# Anthophora.net
KiCad netlist of a schematic drawn in EAGLE
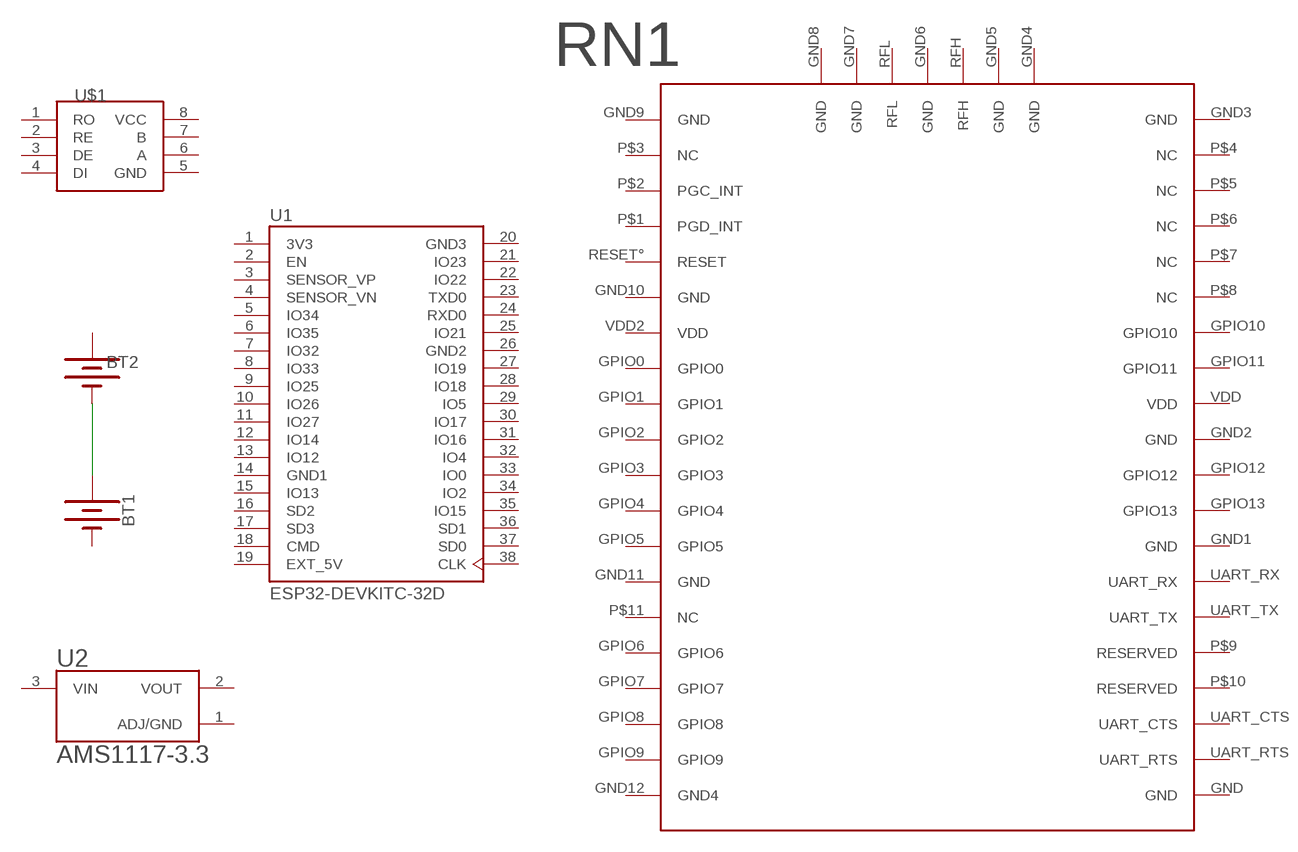
[diagram p0: schematic, sheet 1]

(export (version "E")
  (design (tool "Eeschema 10.0.6"))
  (components
    (comp (ref "BT1")
      (value "BATTERY-AA_KIT")
      (footprint "eagle-import:BATTERY-AA-KIT")
      (libsource (lib "eagle-import") (part "BATTERY-AA_KIT"))
    )
    (comp (ref "BT2")
      (value "BATTERY-AA_KIT")
      (footprint "eagle-import:BATTERY-AA-KIT")
      (libsource (lib "eagle-import") (part "BATTERY-AA_KIT"))
    )
    (comp (ref "RN1")
      (value "NEW_RN2483")
      (footprint "eagle-import:NEW_RN2483")
      (libsource (lib "eagle-import") (part "NEW_RN2483"))
    )
    (comp (ref "U$1")
      (value "AMD3485E")
      (footprint "eagle-import:AMD3485E")
      (libsource (lib "eagle-import") (part "AMD3485E"))
    )
    (comp (ref "U1")
      (value "ESP32-DEVKITC-32D")
      (footprint "eagle-import:MODULE_ESP32-DEVKITC-32D")
      (fields (field (name "MF") "Espressif Systems"))
      (libsource (lib "eagle-import") (part "ESP32-DEVKITC-32D"))
    )
    (comp (ref "U2")
      (value "AMS1117-3.3")
      (footprint "eagle-import:SOT229P700X180-4N")
      (fields (field (name "MF") "Advanced Monolithic Systems"))
      (libsource (lib "eagle-import") (part "AMS1117-3.3"))
    )
  )
  (nets
    (net (code "1") (name "/+") (class "Default")
      (node (ref "BT2") (pin "PWR@1") (pinfunction "+_PWR@1") (pintype "power_in"))
    )
    (net (code "2") (name "/-") (class "Default")
      (node (ref "BT1") (pin "GND@1") (pinfunction "-_GND@1") (pintype "power_in"))
    )
    (net (code "3") (name "/3V3") (class "Default")
      (node (ref "U1") (pin "1") (pinfunction "3V3_1") (pintype "power_in"))
    )
    (net (code "4") (name "/ADJ{slash}GND") (class "Default")
      (node (ref "U2") (pin "1") (pinfunction "ADJ/GND_1") (pintype "power_in"))
    )
    (net (code "5") (name "/EXT_5V") (class "Default")
      (node (ref "U1") (pin "19") (pinfunction "EXT_5V_19") (pintype "power_in"))
    )
    (net (code "6") (name "/GND1") (class "Default")
      (node (ref "U1") (pin "14") (pinfunction "GND1_14") (pintype "power_in"))
    )
    (net (code "7") (name "/GND2") (class "Default")
      (node (ref "U1") (pin "26") (pinfunction "GND2_26") (pintype "power_in"))
    )
    (net (code "8") (name "/GND3") (class "Default")
      (node (ref "U1") (pin "20") (pinfunction "GND3_20") (pintype "power_in"))
    )
    (net (code "9") (name "Net-(BT1-+)") (class "Default")
      (node (ref "BT1") (pin "PWR@1") (pinfunction "+_PWR@1") (pintype "power_in"))
      (node (ref "BT2") (pin "GND@1") (pinfunction "-_GND@1") (pintype "power_in"))
    )
    (net (code "10") (name "unconnected-(RN1-GND-PadGND1)") (class "Default")
      (node (ref "RN1") (pin "GND1") (pinfunction "GND_GND1") (pintype "bidirectional"))
    )
    (net (code "11") (name "unconnected-(RN1-GND-PadGND2)") (class "Default")
      (node (ref "RN1") (pin "GND2") (pinfunction "GND_GND2") (pintype "bidirectional"))
    )
    (net (code "12") (name "unconnected-(RN1-GND-PadGND3)") (class "Default")
      (node (ref "RN1") (pin "GND3") (pinfunction "GND_GND3") (pintype "bidirectional"))
    )
    (net (code "13") (name "unconnected-(RN1-GND-PadGND4)") (class "Default")
      (node (ref "RN1") (pin "GND4") (pinfunction "GND_GND4") (pintype "bidirectional"))
    )
    (net (code "14") (name "unconnected-(RN1-GND-PadGND5)") (class "Default")
      (node (ref "RN1") (pin "GND5") (pinfunction "GND_GND5") (pintype "bidirectional"))
    )
    (net (code "15") (name "unconnected-(RN1-GND-PadGND6)") (class "Default")
      (node (ref "RN1") (pin "GND6") (pinfunction "GND_GND6") (pintype "bidirectional"))
    )
    (net (code "16") (name "unconnected-(RN1-GND-PadGND7)") (class "Default")
      (node (ref "RN1") (pin "GND7") (pinfunction "GND_GND7") (pintype "bidirectional"))
    )
    (net (code "17") (name "unconnected-(RN1-GND-PadGND8)") (class "Default")
      (node (ref "RN1") (pin "GND8") (pinfunction "GND_GND8") (pintype "bidirectional"))
    )
    (net (code "18") (name "unconnected-(RN1-GND-PadGND9)") (class "Default")
      (node (ref "RN1") (pin "GND9") (pinfunction "GND_GND9") (pintype "bidirectional"))
    )
    (net (code "19") (name "unconnected-(RN1-GND-PadGND10)") (class "Default")
      (node (ref "RN1") (pin "GND10") (pinfunction "GND_GND10") (pintype "bidirectional"))
    )
    (net (code "20") (name "unconnected-(RN1-GND-PadGND11)") (class "Default")
      (node (ref "RN1") (pin "GND11") (pinfunction "GND_GND11") (pintype "bidirectional"))
    )
    (net (code "21") (name "unconnected-(RN1-GND4-PadGND12)") (class "Default")
      (node (ref "RN1") (pin "GND12") (pinfunction "GND4_GND12") (pintype "bidirectional"))
    )
    (net (code "22") (name "unconnected-(RN1-NC-PadP$3)") (class "Default")
      (node (ref "RN1") (pin "P$3") (pinfunction "NC_P$3") (pintype "bidirectional"))
    )
    (net (code "23") (name "unconnected-(RN1-NC-PadP$4)") (class "Default")
      (node (ref "RN1") (pin "P$4") (pinfunction "NC_P$4") (pintype "bidirectional"))
    )
    (net (code "24") (name "unconnected-(RN1-NC-PadP$5)") (class "Default")
      (node (ref "RN1") (pin "P$5") (pinfunction "NC_P$5") (pintype "bidirectional"))
    )
    (net (code "25") (name "unconnected-(RN1-NC-PadP$6)") (class "Default")
      (node (ref "RN1") (pin "P$6") (pinfunction "NC_P$6") (pintype "bidirectional"))
    )
    (net (code "26") (name "unconnected-(RN1-NC-PadP$7)") (class "Default")
      (node (ref "RN1") (pin "P$7") (pinfunction "NC_P$7") (pintype "bidirectional"))
    )
    (net (code "27") (name "unconnected-(RN1-NC-PadP$8)") (class "Default")
      (node (ref "RN1") (pin "P$8") (pinfunction "NC_P$8") (pintype "bidirectional"))
    )
    (net (code "28") (name "unconnected-(RN1-NC-PadP$11)") (class "Default")
      (node (ref "RN1") (pin "P$11") (pinfunction "NC_P$11") (pintype "bidirectional"))
    )
    (net (code "29") (name "unconnected-(RN1-PGC_INT-PadP$2)") (class "Default")
      (node (ref "RN1") (pin "P$2") (pinfunction "PGC_INT_P$2") (pintype "bidirectional"))
    )
    (net (code "30") (name "unconnected-(RN1-PGD_INT-PadP$1)") (class "Default")
      (node (ref "RN1") (pin "P$1") (pinfunction "PGD_INT_P$1") (pintype "bidirectional"))
    )
    (net (code "31") (name "unconnected-(RN1-PadGND)") (class "Default")
      (node (ref "RN1") (pin "GND") (pinfunction "GND_GND") (pintype "bidirectional"))
    )
    (net (code "32") (name "unconnected-(RN1-PadGPIO0)") (class "Default")
      (node (ref "RN1") (pin "GPIO0") (pinfunction "GPIO0_GPIO0") (pintype "bidirectional"))
    )
    (net (code "33") (name "unconnected-(RN1-PadGPIO1)") (class "Default")
      (node (ref "RN1") (pin "GPIO1") (pinfunction "GPIO1_GPIO1") (pintype "bidirectional"))
    )
    (net (code "34") (name "unconnected-(RN1-PadGPIO2)") (class "Default")
      (node (ref "RN1") (pin "GPIO2") (pinfunction "GPIO2_GPIO2") (pintype "bidirectional"))
    )
    (net (code "35") (name "unconnected-(RN1-PadGPIO3)") (class "Default")
      (node (ref "RN1") (pin "GPIO3") (pinfunction "GPIO3_GPIO3") (pintype "bidirectional"))
    )
    (net (code "36") (name "unconnected-(RN1-PadGPIO4)") (class "Default")
      (node (ref "RN1") (pin "GPIO4") (pinfunction "GPIO4_GPIO4") (pintype "bidirectional"))
    )
    (net (code "37") (name "unconnected-(RN1-PadGPIO5)") (class "Default")
      (node (ref "RN1") (pin "GPIO5") (pinfunction "GPIO5_GPIO5") (pintype "bidirectional"))
    )
    (net (code "38") (name "unconnected-(RN1-PadGPIO6)") (class "Default")
      (node (ref "RN1") (pin "GPIO6") (pinfunction "GPIO6_GPIO6") (pintype "bidirectional"))
    )
    (net (code "39") (name "unconnected-(RN1-PadGPIO7)") (class "Default")
      (node (ref "RN1") (pin "GPIO7") (pinfunction "GPIO7_GPIO7") (pintype "bidirectional"))
    )
    (net (code "40") (name "unconnected-(RN1-PadGPIO8)") (class "Default")
      (node (ref "RN1") (pin "GPIO8") (pinfunction "GPIO8_GPIO8") (pintype "bidirectional"))
    )
    (net (code "41") (name "unconnected-(RN1-PadGPIO9)") (class "Default")
      (node (ref "RN1") (pin "GPIO9") (pinfunction "GPIO9_GPIO9") (pintype "bidirectional"))
    )
    (net (code "42") (name "unconnected-(RN1-PadGPIO10)") (class "Default")
      (node (ref "RN1") (pin "GPIO10") (pinfunction "GPIO10_GPIO10") (pintype "bidirectional"))
    )
    (net (code "43") (name "unconnected-(RN1-PadGPIO11)") (class "Default")
      (node (ref "RN1") (pin "GPIO11") (pinfunction "GPIO11_GPIO11") (pintype "bidirectional"))
    )
    (net (code "44") (name "unconnected-(RN1-PadGPIO12)") (class "Default")
      (node (ref "RN1") (pin "GPIO12") (pinfunction "GPIO12_GPIO12") (pintype "bidirectional"))
    )
    (net (code "45") (name "unconnected-(RN1-PadGPIO13)") (class "Default")
      (node (ref "RN1") (pin "GPIO13") (pinfunction "GPIO13_GPIO13") (pintype "bidirectional"))
    )
    (net (code "46") (name "unconnected-(RN1-PadRFH)") (class "Default")
      (node (ref "RN1") (pin "RFH") (pinfunction "RFH_RFH") (pintype "bidirectional"))
    )
    (net (code "47") (name "unconnected-(RN1-PadRFL)") (class "Default")
      (node (ref "RN1") (pin "RFL") (pinfunction "RFL_RFL") (pintype "bidirectional"))
    )
    (net (code "48") (name "unconnected-(RN1-PadUART_CTS)") (class "Default")
      (node (ref "RN1") (pin "UART_CTS") (pinfunction "UART_CTS_UART_CTS") (pintype "bidirectional"))
    )
    (net (code "49") (name "unconnected-(RN1-PadUART_RTS)") (class "Default")
      (node (ref "RN1") (pin "UART_RTS") (pinfunction "UART_RTS_UART_RTS") (pintype "bidirectional"))
    )
    (net (code "50") (name "unconnected-(RN1-PadUART_RX)") (class "Default")
      (node (ref "RN1") (pin "UART_RX") (pinfunction "UART_RX_UART_RX") (pintype "bidirectional"))
    )
    (net (code "51") (name "unconnected-(RN1-PadUART_TX)") (class "Default")
      (node (ref "RN1") (pin "UART_TX") (pinfunction "UART_TX_UART_TX") (pintype "bidirectional"))
    )
    (net (code "52") (name "unconnected-(RN1-PadVDD)") (class "Default")
      (node (ref "RN1") (pin "VDD") (pinfunction "VDD_VDD") (pintype "bidirectional"))
    )
    (net (code "53") (name "unconnected-(RN1-RESERVED-PadP$9)") (class "Default")
      (node (ref "RN1") (pin "P$9") (pinfunction "RESERVED_P$9") (pintype "bidirectional"))
    )
    (net (code "54") (name "unconnected-(RN1-RESERVED-PadP$10)") (class "Default")
      (node (ref "RN1") (pin "P$10") (pinfunction "RESERVED_P$10") (pintype "bidirectional"))
    )
    (net (code "55") (name "unconnected-(RN1-RESET-PadRESET°)") (class "Default")
      (node (ref "RN1") (pin "RESET°") (pinfunction "RESET_RESET°") (pintype "bidirectional"))
    )
    (net (code "56") (name "unconnected-(RN1-VDD-PadVDD2)") (class "Default")
      (node (ref "RN1") (pin "VDD2") (pinfunction "VDD_VDD2") (pintype "bidirectional"))
    )
    (net (code "57") (name "unconnected-(U$1-A-Pad6)") (class "Default")
      (node (ref "U$1") (pin "6") (pinfunction "A_6") (pintype "bidirectional"))
    )
    (net (code "58") (name "unconnected-(U$1-B-Pad7)") (class "Default")
      (node (ref "U$1") (pin "7") (pinfunction "B_7") (pintype "bidirectional"))
    )
    (net (code "59") (name "unconnected-(U$1-DE-Pad3)") (class "Default")
      (node (ref "U$1") (pin "3") (pinfunction "DE_3") (pintype "bidirectional"))
    )
    (net (code "60") (name "unconnected-(U$1-DI-Pad4)") (class "Default")
      (node (ref "U$1") (pin "4") (pinfunction "DI_4") (pintype "bidirectional"))
    )
    (net (code "61") (name "unconnected-(U$1-GND-Pad5)") (class "Default")
      (node (ref "U$1") (pin "5") (pinfunction "GND_5") (pintype "bidirectional"))
    )
    (net (code "62") (name "unconnected-(U$1-RE-Pad2)") (class "Default")
      (node (ref "U$1") (pin "2") (pinfunction "RE_2") (pintype "bidirectional"))
    )
    (net (code "63") (name "unconnected-(U$1-RO-Pad1)") (class "Default")
      (node (ref "U$1") (pin "1") (pinfunction "RO_1") (pintype "bidirectional"))
    )
    (net (code "64") (name "unconnected-(U$1-VCC-Pad8)") (class "Default")
      (node (ref "U$1") (pin "8") (pinfunction "VCC_8") (pintype "bidirectional"))
    )
    (net (code "65") (name "unconnected-(U1-CLK-Pad38)") (class "Default")
      (node (ref "U1") (pin "38") (pinfunction "CLK_38") (pintype "input"))
    )
    (net (code "66") (name "unconnected-(U1-CMD-Pad18)") (class "Default")
      (node (ref "U1") (pin "18") (pinfunction "CMD_18") (pintype "bidirectional"))
    )
    (net (code "67") (name "unconnected-(U1-EN-Pad2)") (class "Default")
      (node (ref "U1") (pin "2") (pinfunction "EN_2") (pintype "input"))
    )
    (net (code "68") (name "unconnected-(U1-IO0-Pad33)") (class "Default")
      (node (ref "U1") (pin "33") (pinfunction "IO0_33") (pintype "bidirectional"))
    )
    (net (code "69") (name "unconnected-(U1-IO2-Pad34)") (class "Default")
      (node (ref "U1") (pin "34") (pinfunction "IO2_34") (pintype "bidirectional"))
    )
    (net (code "70") (name "unconnected-(U1-IO4-Pad32)") (class "Default")
      (node (ref "U1") (pin "32") (pinfunction "IO4_32") (pintype "bidirectional"))
    )
    (net (code "71") (name "unconnected-(U1-IO5-Pad29)") (class "Default")
      (node (ref "U1") (pin "29") (pinfunction "IO5_29") (pintype "bidirectional"))
    )
    (net (code "72") (name "unconnected-(U1-IO12-Pad13)") (class "Default")
      (node (ref "U1") (pin "13") (pinfunction "IO12_13") (pintype "bidirectional"))
    )
    (net (code "73") (name "unconnected-(U1-IO13-Pad15)") (class "Default")
      (node (ref "U1") (pin "15") (pinfunction "IO13_15") (pintype "bidirectional"))
    )
    (net (code "74") (name "unconnected-(U1-IO14-Pad12)") (class "Default")
      (node (ref "U1") (pin "12") (pinfunction "IO14_12") (pintype "bidirectional"))
    )
    (net (code "75") (name "unconnected-(U1-IO15-Pad35)") (class "Default")
      (node (ref "U1") (pin "35") (pinfunction "IO15_35") (pintype "bidirectional"))
    )
    (net (code "76") (name "unconnected-(U1-IO16-Pad31)") (class "Default")
      (node (ref "U1") (pin "31") (pinfunction "IO16_31") (pintype "bidirectional"))
    )
    (net (code "77") (name "unconnected-(U1-IO17-Pad30)") (class "Default")
      (node (ref "U1") (pin "30") (pinfunction "IO17_30") (pintype "bidirectional"))
    )
    (net (code "78") (name "unconnected-(U1-IO18-Pad28)") (class "Default")
      (node (ref "U1") (pin "28") (pinfunction "IO18_28") (pintype "bidirectional"))
    )
    (net (code "79") (name "unconnected-(U1-IO19-Pad27)") (class "Default")
      (node (ref "U1") (pin "27") (pinfunction "IO19_27") (pintype "bidirectional"))
    )
    (net (code "80") (name "unconnected-(U1-IO21-Pad25)") (class "Default")
      (node (ref "U1") (pin "25") (pinfunction "IO21_25") (pintype "bidirectional"))
    )
    (net (code "81") (name "unconnected-(U1-IO22-Pad22)") (class "Default")
      (node (ref "U1") (pin "22") (pinfunction "IO22_22") (pintype "bidirectional"))
    )
    (net (code "82") (name "unconnected-(U1-IO23-Pad21)") (class "Default")
      (node (ref "U1") (pin "21") (pinfunction "IO23_21") (pintype "bidirectional"))
    )
    (net (code "83") (name "unconnected-(U1-IO25-Pad9)") (class "Default")
      (node (ref "U1") (pin "9") (pinfunction "IO25_9") (pintype "bidirectional"))
    )
    (net (code "84") (name "unconnected-(U1-IO26-Pad10)") (class "Default")
      (node (ref "U1") (pin "10") (pinfunction "IO26_10") (pintype "bidirectional"))
    )
    (net (code "85") (name "unconnected-(U1-IO27-Pad11)") (class "Default")
      (node (ref "U1") (pin "11") (pinfunction "IO27_11") (pintype "bidirectional"))
    )
    (net (code "86") (name "unconnected-(U1-IO32-Pad7)") (class "Default")
      (node (ref "U1") (pin "7") (pinfunction "IO32_7") (pintype "bidirectional"))
    )
    (net (code "87") (name "unconnected-(U1-IO33-Pad8)") (class "Default")
      (node (ref "U1") (pin "8") (pinfunction "IO33_8") (pintype "bidirectional"))
    )
    (net (code "88") (name "unconnected-(U1-IO34-Pad5)") (class "Default")
      (node (ref "U1") (pin "5") (pinfunction "IO34_5") (pintype "bidirectional"))
    )
    (net (code "89") (name "unconnected-(U1-IO35-Pad6)") (class "Default")
      (node (ref "U1") (pin "6") (pinfunction "IO35_6") (pintype "bidirectional"))
    )
    (net (code "90") (name "unconnected-(U1-RXD0-Pad24)") (class "Default")
      (node (ref "U1") (pin "24") (pinfunction "RXD0_24") (pintype "input"))
    )
    (net (code "91") (name "unconnected-(U1-SD0-Pad37)") (class "Default")
      (node (ref "U1") (pin "37") (pinfunction "SD0_37") (pintype "bidirectional"))
    )
    (net (code "92") (name "unconnected-(U1-SD1-Pad36)") (class "Default")
      (node (ref "U1") (pin "36") (pinfunction "SD1_36") (pintype "bidirectional"))
    )
    (net (code "93") (name "unconnected-(U1-SD2-Pad16)") (class "Default")
      (node (ref "U1") (pin "16") (pinfunction "SD2_16") (pintype "bidirectional"))
    )
    (net (code "94") (name "unconnected-(U1-SD3-Pad17)") (class "Default")
      (node (ref "U1") (pin "17") (pinfunction "SD3_17") (pintype "bidirectional"))
    )
    (net (code "95") (name "unconnected-(U1-SENSOR_VN-Pad4)") (class "Default")
      (node (ref "U1") (pin "4") (pinfunction "SENSOR_VN_4") (pintype "input"))
    )
    (net (code "96") (name "unconnected-(U1-SENSOR_VP-Pad3)") (class "Default")
      (node (ref "U1") (pin "3") (pinfunction "SENSOR_VP_3") (pintype "input"))
    )
    (net (code "97") (name "unconnected-(U1-TXD0-Pad23)") (class "Default")
      (node (ref "U1") (pin "23") (pinfunction "TXD0_23") (pintype "output"))
    )
    (net (code "98") (name "unconnected-(U2-VIN-Pad3)") (class "Default")
      (node (ref "U2") (pin "3") (pinfunction "VIN_3") (pintype "input"))
    )
    (net (code "99") (name "unconnected-(U2-VOUT-Pad2)") (class "Default")
      (node (ref "U2") (pin "2") (pinfunction "VOUT_2") (pintype "output"))
    )
  )
)
